# Sheet1.net
KiCad netlist of a schematic drawn in Altium Designer
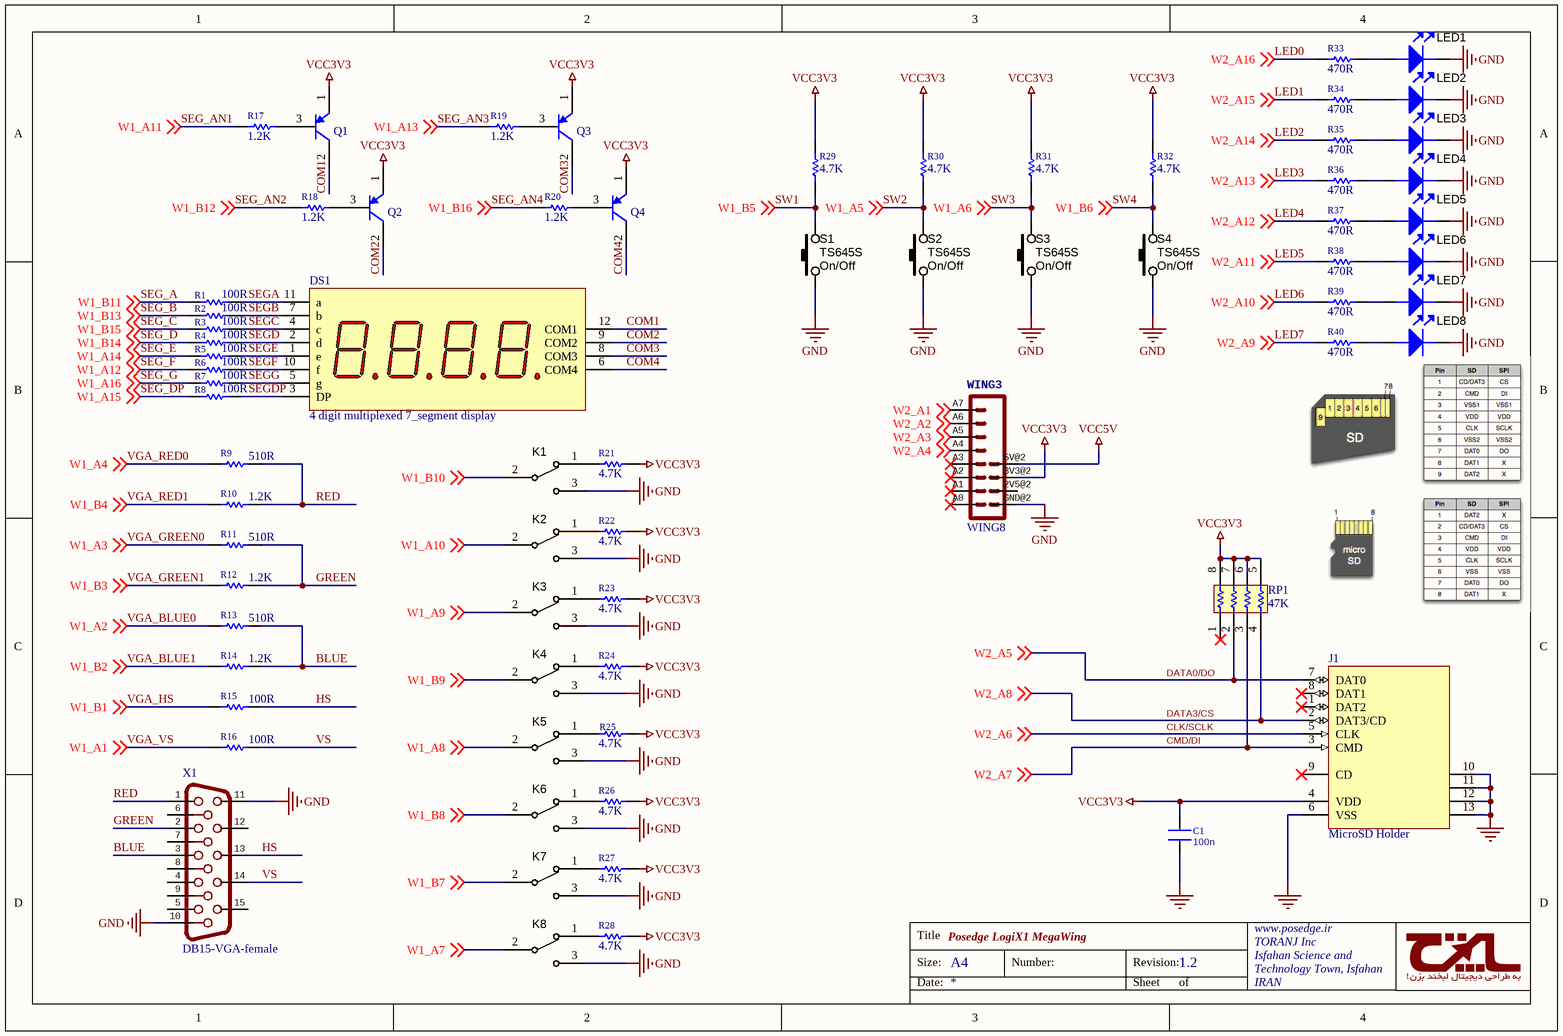
[diagram p0: Sheet1.SchDoc]

(export (version "E")
  (design (tool "Eeschema 10.0.6"))
  (components
    (comp (ref "C1")
      (value "100n")
      (footprint "C0805_M")
      (description "Ceramic Capactor size 0805")
      (libsource (lib "MH - RCLDSX") (part "C0805"))
    )
    (comp (ref "DS1")
      (value "4 digit multiplexed 7_segment display")
      (footprint "7SEG-MPX4-CA")
      (description "7-Segment 4-Digits")
      (libsource (lib "MH - RCLDSX") (part "7SEG-MPX4-CA"))
    )
    (comp (ref "J1")
      (value "MicroSD Holder")
      (footprint "micro sd soket")
      (description "MicroSD Memory Card Holder")
      (libsource (lib "MH - Connectors") (part "MicroSD"))
    )
    (comp (ref "K1")
      (value "Slide Switch 3Pin")
      (footprint "SWITCH_SPDT_SLIDER")
      (description "Switch THD vertical toggle SPDT")
      (libsource (lib "PBL - Switches") (part "SW_THD_SPDT_On-On"))
    )
    (comp (ref "K2")
      (value "Slide Switch 3Pin")
      (footprint "SWITCH_SPDT_SLIDER")
      (description "Switch THD vertical toggle SPDT")
      (libsource (lib "PBL - Switches") (part "SW_THD_SPDT_On-On"))
    )
    (comp (ref "K3")
      (value "Slide Switch 3Pin")
      (footprint "SWITCH_SPDT_SLIDER")
      (description "Switch THD vertical toggle SPDT")
      (libsource (lib "PBL - Switches") (part "SW_THD_SPDT_On-On"))
    )
    (comp (ref "K4")
      (value "Slide Switch 3Pin")
      (footprint "SWITCH_SPDT_SLIDER")
      (description "Switch THD vertical toggle SPDT")
      (libsource (lib "PBL - Switches") (part "SW_THD_SPDT_On-On"))
    )
    (comp (ref "K5")
      (value "Slide Switch 3Pin")
      (footprint "SWITCH_SPDT_SLIDER")
      (description "Switch THD vertical toggle SPDT")
      (libsource (lib "PBL - Switches") (part "SW_THD_SPDT_On-On"))
    )
    (comp (ref "K6")
      (value "Slide Switch 3Pin")
      (footprint "SWITCH_SPDT_SLIDER")
      (description "Switch THD vertical toggle SPDT")
      (libsource (lib "PBL - Switches") (part "SW_THD_SPDT_On-On"))
    )
    (comp (ref "K7")
      (value "Slide Switch 3Pin")
      (footprint "SWITCH_SPDT_SLIDER")
      (description "Switch THD vertical toggle SPDT")
      (libsource (lib "PBL - Switches") (part "SW_THD_SPDT_On-On"))
    )
    (comp (ref "K8")
      (value "Slide Switch 3Pin")
      (footprint "SWITCH_SPDT_SLIDER")
      (description "Switch THD vertical toggle SPDT")
      (libsource (lib "PBL - Switches") (part "SW_THD_SPDT_On-On"))
    )
    (comp (ref "LED1")
      (value "~")
      (footprint "LED_0805")
      (description "LED, 0805 SMD")
      (libsource (lib "MH - RCLDSX") (part "LED_0805"))
    )
    (comp (ref "LED2")
      (value "~")
      (footprint "LED_0805")
      (description "LED, 0805 SMD")
      (libsource (lib "MH - RCLDSX") (part "LED_0805"))
    )
    (comp (ref "LED3")
      (value "~")
      (footprint "LED_0805")
      (description "LED, 0805 SMD")
      (libsource (lib "MH - RCLDSX") (part "LED_0805"))
    )
    (comp (ref "LED4")
      (value "~")
      (footprint "LED_0805")
      (description "LED, 0805 SMD")
      (libsource (lib "MH - RCLDSX") (part "LED_0805"))
    )
    (comp (ref "LED5")
      (value "~")
      (footprint "LED_0805")
      (description "LED, 0805 SMD")
      (libsource (lib "MH - RCLDSX") (part "LED_0805"))
    )
    (comp (ref "LED6")
      (value "~")
      (footprint "LED_0805")
      (description "LED, 0805 SMD")
      (libsource (lib "MH - RCLDSX") (part "LED_0805"))
    )
    (comp (ref "LED7")
      (value "~")
      (footprint "LED_0805")
      (description "LED, 0805 SMD")
      (libsource (lib "MH - RCLDSX") (part "LED_0805"))
    )
    (comp (ref "LED8")
      (value "~")
      (footprint "LED_0805")
      (description "LED, 0805 SMD")
      (libsource (lib "MH - RCLDSX") (part "LED_0805"))
    )
    (comp (ref "Q1")
      (value "A733")
      (footprint "TO-92")
      (description "PNP Bipolar Transistor")
      (libsource (lib "MH - RCLDSX") (part "A733"))
    )
    (comp (ref "Q2")
      (value "A733")
      (footprint "TO-92")
      (description "PNP Bipolar Transistor")
      (libsource (lib "MH - RCLDSX") (part "A733"))
    )
    (comp (ref "Q3")
      (value "A733")
      (footprint "TO-92")
      (description "PNP Bipolar Transistor")
      (libsource (lib "MH - RCLDSX") (part "A733"))
    )
    (comp (ref "Q4")
      (value "A733")
      (footprint "TO-92")
      (description "PNP Bipolar Transistor")
      (libsource (lib "MH - RCLDSX") (part "A733"))
    )
    (comp (ref "R1")
      (value "100R")
      (footprint "R0805_M")
      (description "Chip Resistor size 0805")
      (libsource (lib "MH - RCLDSX") (part "R0805"))
    )
    (comp (ref "R2")
      (value "100R")
      (footprint "R0805_M")
      (description "Chip Resistor size 0805")
      (libsource (lib "MH - RCLDSX") (part "R0805"))
    )
    (comp (ref "R3")
      (value "100R")
      (footprint "R0805_M")
      (description "Chip Resistor size 0805")
      (libsource (lib "MH - RCLDSX") (part "R0805"))
    )
    (comp (ref "R4")
      (value "100R")
      (footprint "R0805_M")
      (description "Chip Resistor size 0805")
      (libsource (lib "MH - RCLDSX") (part "R0805"))
    )
    (comp (ref "R5")
      (value "100R")
      (footprint "R0805_M")
      (description "Chip Resistor size 0805")
      (libsource (lib "MH - RCLDSX") (part "R0805"))
    )
    (comp (ref "R6")
      (value "100R")
      (footprint "R0805_M")
      (description "Chip Resistor size 0805")
      (libsource (lib "MH - RCLDSX") (part "R0805"))
    )
    (comp (ref "R7")
      (value "100R")
      (footprint "R0805_M")
      (description "Chip Resistor size 0805")
      (libsource (lib "MH - RCLDSX") (part "R0805"))
    )
    (comp (ref "R8")
      (value "100R")
      (footprint "R0805_M")
      (description "Chip Resistor size 0805")
      (libsource (lib "MH - RCLDSX") (part "R0805"))
    )
    (comp (ref "R9")
      (value "510R")
      (footprint "R0805_M")
      (description "Chip Resistor size 0805")
      (libsource (lib "MH - RCLDSX") (part "R0805"))
    )
    (comp (ref "R10")
      (value "1.2K")
      (footprint "R0805_M")
      (description "Chip Resistor size 0805")
      (libsource (lib "MH - RCLDSX") (part "R0805"))
    )
    (comp (ref "R11")
      (value "510R")
      (footprint "R0805_M")
      (description "Chip Resistor size 0805")
      (libsource (lib "MH - RCLDSX") (part "R0805"))
    )
    (comp (ref "R12")
      (value "1.2K")
      (footprint "R0805_M")
      (description "Chip Resistor size 0805")
      (libsource (lib "MH - RCLDSX") (part "R0805"))
    )
    (comp (ref "R13")
      (value "510R")
      (footprint "R0805_M")
      (description "Chip Resistor size 0805")
      (libsource (lib "MH - RCLDSX") (part "R0805"))
    )
    (comp (ref "R14")
      (value "1.2K")
      (footprint "R0805_M")
      (description "Chip Resistor size 0805")
      (libsource (lib "MH - RCLDSX") (part "R0805"))
    )
    (comp (ref "R15")
      (value "100R")
      (footprint "R0805_M")
      (description "Chip Resistor size 0805")
      (libsource (lib "MH - RCLDSX") (part "R0805"))
    )
    (comp (ref "R16")
      (value "100R")
      (footprint "R0805_M")
      (description "Chip Resistor size 0805")
      (libsource (lib "MH - RCLDSX") (part "R0805"))
    )
    (comp (ref "R17")
      (value "1.2K")
      (footprint "R0805_M")
      (description "Chip Resistor size 0805")
      (libsource (lib "MH - RCLDSX") (part "R0805"))
    )
    (comp (ref "R18")
      (value "1.2K")
      (footprint "R0805_M")
      (description "Chip Resistor size 0805")
      (libsource (lib "MH - RCLDSX") (part "R0805"))
    )
    (comp (ref "R19")
      (value "1.2K")
      (footprint "R0805_M")
      (description "Chip Resistor size 0805")
      (libsource (lib "MH - RCLDSX") (part "R0805"))
    )
    (comp (ref "R20")
      (value "1.2K")
      (footprint "R0805_M")
      (description "Chip Resistor size 0805")
      (libsource (lib "MH - RCLDSX") (part "R0805"))
    )
    (comp (ref "R21")
      (value "4.7K")
      (footprint "R0805_M")
      (description "Chip Resistor size 0805")
      (libsource (lib "MH - RCLDSX") (part "R0805"))
    )
    (comp (ref "R22")
      (value "4.7K")
      (footprint "R0805_M")
      (description "Chip Resistor size 0805")
      (libsource (lib "MH - RCLDSX") (part "R0805"))
    )
    (comp (ref "R23")
      (value "4.7K")
      (footprint "R0805_M")
      (description "Chip Resistor size 0805")
      (libsource (lib "MH - RCLDSX") (part "R0805"))
    )
    (comp (ref "R24")
      (value "4.7K")
      (footprint "R0805_M")
      (description "Chip Resistor size 0805")
      (libsource (lib "MH - RCLDSX") (part "R0805"))
    )
    (comp (ref "R25")
      (value "4.7K")
      (footprint "R0805_M")
      (description "Chip Resistor size 0805")
      (libsource (lib "MH - RCLDSX") (part "R0805"))
    )
    (comp (ref "R26")
      (value "4.7K")
      (footprint "R0805_M")
      (description "Chip Resistor size 0805")
      (libsource (lib "MH - RCLDSX") (part "R0805"))
    )
    (comp (ref "R27")
      (value "4.7K")
      (footprint "R0805_M")
      (description "Chip Resistor size 0805")
      (libsource (lib "MH - RCLDSX") (part "R0805"))
    )
    (comp (ref "R28")
      (value "4.7K")
      (footprint "R0805_M")
      (description "Chip Resistor size 0805")
      (libsource (lib "MH - RCLDSX") (part "R0805"))
    )
    (comp (ref "R29")
      (value "4.7K")
      (footprint "R0805_M")
      (description "Chip Resistor size 0805")
      (libsource (lib "MH - RCLDSX") (part "R0805"))
    )
    (comp (ref "R30")
      (value "4.7K")
      (footprint "R0805_M")
      (description "Chip Resistor size 0805")
      (libsource (lib "MH - RCLDSX") (part "R0805"))
    )
    (comp (ref "R31")
      (value "4.7K")
      (footprint "R0805_M")
      (description "Chip Resistor size 0805")
      (libsource (lib "MH - RCLDSX") (part "R0805"))
    )
    (comp (ref "R32")
      (value "4.7K")
      (footprint "R0805_M")
      (description "Chip Resistor size 0805")
      (libsource (lib "MH - RCLDSX") (part "R0805"))
    )
    (comp (ref "R33")
      (value "470R")
      (footprint "R0805_M")
      (description "Chip Resistor size 0805")
      (libsource (lib "MH - RCLDSX") (part "R0805"))
    )
    (comp (ref "R34")
      (value "470R")
      (footprint "R0805_M")
      (description "Chip Resistor size 0805")
      (libsource (lib "MH - RCLDSX") (part "R0805"))
    )
    (comp (ref "R35")
      (value "470R")
      (footprint "R0805_M")
      (description "Chip Resistor size 0805")
      (libsource (lib "MH - RCLDSX") (part "R0805"))
    )
    (comp (ref "R36")
      (value "470R")
      (footprint "R0805_M")
      (description "Chip Resistor size 0805")
      (libsource (lib "MH - RCLDSX") (part "R0805"))
    )
    (comp (ref "R37")
      (value "470R")
      (footprint "R0805_M")
      (description "Chip Resistor size 0805")
      (libsource (lib "MH - RCLDSX") (part "R0805"))
    )
    (comp (ref "R38")
      (value "470R")
      (footprint "R0805_M")
      (description "Chip Resistor size 0805")
      (libsource (lib "MH - RCLDSX") (part "R0805"))
    )
    (comp (ref "R39")
      (value "470R")
      (footprint "R0805_M")
      (description "Chip Resistor size 0805")
      (libsource (lib "MH - RCLDSX") (part "R0805"))
    )
    (comp (ref "R40")
      (value "470R")
      (footprint "R0805_M")
      (description "Chip Resistor size 0805")
      (libsource (lib "MH - RCLDSX") (part "R0805"))
    )
    (comp (ref "RP1")
      (value "47K")
      (footprint "RESCAXS50P160X320X70-8N")
      (description "Isolated Resistor Network")
      (libsource (lib "MH - RCLDSX") (part "RESPACK_4X"))
    )
    (comp (ref "S1")
      (value "TS645S")
      (footprint "TS645S")
      (description "SMT Tactile Switch (6mm x 6mm)")
      (fields (field (name "FUNCTION") "On/Off"))
      (libsource (lib "MH - RCLDSX") (part "SW_SMD_4Pin"))
    )
    (comp (ref "S2")
      (value "TS645S")
      (footprint "TS645S")
      (description "SMT Tactile Switch (6mm x 6mm)")
      (fields (field (name "FUNCTION") "On/Off"))
      (libsource (lib "MH - RCLDSX") (part "SW_SMD_4Pin"))
    )
    (comp (ref "S3")
      (value "TS645S")
      (footprint "TS645S")
      (description "SMT Tactile Switch (6mm x 6mm)")
      (fields (field (name "FUNCTION") "On/Off"))
      (libsource (lib "MH - RCLDSX") (part "SW_SMD_4Pin"))
    )
    (comp (ref "S4")
      (value "TS645S")
      (footprint "TS645S")
      (description "SMT Tactile Switch (6mm x 6mm)")
      (fields (field (name "FUNCTION") "On/Off"))
      (libsource (lib "MH - RCLDSX") (part "SW_SMD_4Pin"))
    )
    (comp (ref "WING3")
      (value "WING8")
      (footprint "WINGSIDE_8BIT")
      (libsource (lib "Papilio") (part "WING8"))
    )
    (comp (ref "X1")
      (value "DB15-VGA-female")
      (footprint "HDF15H")
      (description "VGA Connector Right angle")
      (libsource (lib "vga") (part "HF15H"))
    )
  )
  (nets
    (net (code "1") (name "/BLUE") (class "Default")
      (node (ref "R13") (pin "1") (pinfunction "1_1") (pintype "passive"))
      (node (ref "R14") (pin "1") (pinfunction "1_1") (pintype "passive"))
      (node (ref "X1") (pin "3") (pinfunction "3_3") (pintype "passive"))
    )
    (net (code "2") (name "/COM1") (class "Default")
      (node (ref "DS1") (pin "12") (pinfunction "COM1_12") (pintype "passive"))
      (node (ref "Q1") (pin "2") (pinfunction "C_2") (pintype "passive"))
    )
    (net (code "3") (name "/COM2") (class "Default")
      (node (ref "DS1") (pin "9") (pinfunction "COM2_9") (pintype "passive"))
      (node (ref "Q2") (pin "2") (pinfunction "C_2") (pintype "passive"))
    )
    (net (code "4") (name "/COM3") (class "Default")
      (node (ref "DS1") (pin "8") (pinfunction "COM3_8") (pintype "passive"))
      (node (ref "Q3") (pin "2") (pinfunction "C_2") (pintype "passive"))
    )
    (net (code "5") (name "/COM4") (class "Default")
      (node (ref "DS1") (pin "6") (pinfunction "COM4_6") (pintype "passive"))
      (node (ref "Q4") (pin "2") (pinfunction "C_2") (pintype "passive"))
    )
    (net (code "6") (name "/GREEN") (class "Default")
      (node (ref "R11") (pin "1") (pinfunction "1_1") (pintype "passive"))
      (node (ref "R12") (pin "1") (pinfunction "1_1") (pintype "passive"))
      (node (ref "X1") (pin "2") (pinfunction "2_2") (pintype "passive"))
    )
    (net (code "7") (name "/HS") (class "Default")
      (node (ref "R15") (pin "1") (pinfunction "1_1") (pintype "passive"))
      (node (ref "X1") (pin "13") (pinfunction "13_13") (pintype "passive"))
    )
    (net (code "8") (name "/RED") (class "Default")
      (node (ref "R10") (pin "1") (pinfunction "1_1") (pintype "passive"))
      (node (ref "R9") (pin "1") (pinfunction "1_1") (pintype "passive"))
      (node (ref "X1") (pin "1") (pinfunction "1_1") (pintype "passive"))
    )
    (net (code "9") (name "/SEGA") (class "Default")
      (node (ref "DS1") (pin "11") (pinfunction "a_11") (pintype "passive"))
      (node (ref "R1") (pin "2") (pinfunction "2_2") (pintype "passive"))
    )
    (net (code "10") (name "/SEGB") (class "Default")
      (node (ref "DS1") (pin "7") (pinfunction "b_7") (pintype "passive"))
      (node (ref "R2") (pin "2") (pinfunction "2_2") (pintype "passive"))
    )
    (net (code "11") (name "/SEGC") (class "Default")
      (node (ref "DS1") (pin "4") (pinfunction "c_4") (pintype "passive"))
      (node (ref "R3") (pin "2") (pinfunction "2_2") (pintype "passive"))
    )
    (net (code "12") (name "/SEGD") (class "Default")
      (node (ref "DS1") (pin "2") (pinfunction "d_2") (pintype "passive"))
      (node (ref "R4") (pin "2") (pinfunction "2_2") (pintype "passive"))
    )
    (net (code "13") (name "/SEGDP") (class "Default")
      (node (ref "DS1") (pin "3") (pinfunction "DP_3") (pintype "passive"))
      (node (ref "R8") (pin "2") (pinfunction "2_2") (pintype "passive"))
    )
    (net (code "14") (name "/SEGE") (class "Default")
      (node (ref "DS1") (pin "1") (pinfunction "e_1") (pintype "passive"))
      (node (ref "R5") (pin "2") (pinfunction "2_2") (pintype "passive"))
    )
    (net (code "15") (name "/SEGF") (class "Default")
      (node (ref "DS1") (pin "10") (pinfunction "f_10") (pintype "passive"))
      (node (ref "R6") (pin "2") (pinfunction "2_2") (pintype "passive"))
    )
    (net (code "16") (name "/SEGG") (class "Default")
      (node (ref "DS1") (pin "5") (pinfunction "g_5") (pintype "passive"))
      (node (ref "R7") (pin "2") (pinfunction "2_2") (pintype "passive"))
    )
    (net (code "17") (name "/VS") (class "Default")
      (node (ref "R16") (pin "1") (pinfunction "1_1") (pintype "passive"))
      (node (ref "X1") (pin "14") (pinfunction "14_14") (pintype "passive"))
    )
    (net (code "18") (name "GND") (class "Default")
      (node (ref "C1") (pin "1") (pintype "passive"))
      (node (ref "J1") (pin "10") (pintype "passive"))
      (node (ref "J1") (pin "11") (pintype "passive"))
      (node (ref "J1") (pin "12") (pintype "passive"))
      (node (ref "J1") (pin "13") (pintype "passive"))
      (node (ref "J1") (pin "6") (pinfunction "VSS_6") (pintype "power_in"))
      (node (ref "K1") (pin "3") (pinfunction "3_3") (pintype "passive"))
      (node (ref "K2") (pin "3") (pinfunction "3_3") (pintype "passive"))
      (node (ref "K3") (pin "3") (pinfunction "3_3") (pintype "passive"))
      (node (ref "K4") (pin "3") (pinfunction "3_3") (pintype "passive"))
      (node (ref "K5") (pin "3") (pinfunction "3_3") (pintype "passive"))
      (node (ref "K6") (pin "3") (pinfunction "3_3") (pintype "passive"))
      (node (ref "K7") (pin "3") (pinfunction "3_3") (pintype "passive"))
      (node (ref "K8") (pin "3") (pinfunction "3_3") (pintype "passive"))
      (node (ref "LED1") (pin "1") (pinfunction "cathode_1") (pintype "passive"))
      (node (ref "LED2") (pin "1") (pinfunction "cathode_1") (pintype "passive"))
      (node (ref "LED3") (pin "1") (pinfunction "cathode_1") (pintype "passive"))
      (node (ref "LED4") (pin "1") (pinfunction "cathode_1") (pintype "passive"))
      (node (ref "LED5") (pin "1") (pinfunction "cathode_1") (pintype "passive"))
      (node (ref "LED6") (pin "1") (pinfunction "cathode_1") (pintype "passive"))
      (node (ref "LED7") (pin "1") (pinfunction "cathode_1") (pintype "passive"))
      (node (ref "LED8") (pin "1") (pinfunction "cathode_1") (pintype "passive"))
      (node (ref "S1") (pin "1") (pintype "passive"))
      (node (ref "S2") (pin "1") (pintype "passive"))
      (node (ref "S3") (pin "1") (pintype "passive"))
      (node (ref "S4") (pin "1") (pintype "passive"))
      (node (ref "WING3") (pin "GND@2") (pinfunction "GND_GND@2") (pintype "passive"))
      (node (ref "X1") (pin "10") (pinfunction "10_10") (pintype "passive"))
      (node (ref "X1") (pin "11") (pinfunction "11_11") (pintype "passive"))
    )
    (net (code "19") (name "Net-(K1-Pad1)") (class "Default")
      (node (ref "K1") (pin "1") (pinfunction "1_1") (pintype "passive"))
      (node (ref "R21") (pin "2") (pinfunction "2_2") (pintype "passive"))
    )
    (net (code "20") (name "Net-(K2-Pad1)") (class "Default")
      (node (ref "K2") (pin "1") (pinfunction "1_1") (pintype "passive"))
      (node (ref "R22") (pin "2") (pinfunction "2_2") (pintype "passive"))
    )
    (net (code "21") (name "Net-(K3-Pad1)") (class "Default")
      (node (ref "K3") (pin "1") (pinfunction "1_1") (pintype "passive"))
      (node (ref "R23") (pin "2") (pinfunction "2_2") (pintype "passive"))
    )
    (net (code "22") (name "Net-(K4-Pad1)") (class "Default")
      (node (ref "K4") (pin "1") (pinfunction "1_1") (pintype "passive"))
      (node (ref "R24") (pin "2") (pinfunction "2_2") (pintype "passive"))
    )
    (net (code "23") (name "Net-(K5-Pad1)") (class "Default")
      (node (ref "K5") (pin "1") (pinfunction "1_1") (pintype "passive"))
      (node (ref "R25") (pin "2") (pinfunction "2_2") (pintype "passive"))
    )
    (net (code "24") (name "Net-(K6-Pad1)") (class "Default")
      (node (ref "K6") (pin "1") (pinfunction "1_1") (pintype "passive"))
      (node (ref "R26") (pin "2") (pinfunction "2_2") (pintype "passive"))
    )
    (net (code "25") (name "Net-(K7-Pad1)") (class "Default")
      (node (ref "K7") (pin "1") (pinfunction "1_1") (pintype "passive"))
      (node (ref "R27") (pin "2") (pinfunction "2_2") (pintype "passive"))
    )
    (net (code "26") (name "Net-(K8-Pad1)") (class "Default")
      (node (ref "K8") (pin "1") (pinfunction "1_1") (pintype "passive"))
      (node (ref "R28") (pin "2") (pinfunction "2_2") (pintype "passive"))
    )
    (net (code "27") (name "Net-(LED1-ANODE)") (class "Default")
      (node (ref "LED1") (pin "2") (pinfunction "ANODE_2") (pintype "passive"))
      (node (ref "R33") (pin "1") (pinfunction "1_1") (pintype "passive"))
    )
    (net (code "28") (name "Net-(LED2-ANODE)") (class "Default")
      (node (ref "LED2") (pin "2") (pinfunction "ANODE_2") (pintype "passive"))
      (node (ref "R34") (pin "1") (pinfunction "1_1") (pintype "passive"))
    )
    (net (code "29") (name "Net-(LED3-ANODE)") (class "Default")
      (node (ref "LED3") (pin "2") (pinfunction "ANODE_2") (pintype "passive"))
      (node (ref "R35") (pin "1") (pinfunction "1_1") (pintype "passive"))
    )
    (net (code "30") (name "Net-(LED4-ANODE)") (class "Default")
      (node (ref "LED4") (pin "2") (pinfunction "ANODE_2") (pintype "passive"))
      (node (ref "R36") (pin "1") (pinfunction "1_1") (pintype "passive"))
    )
    (net (code "31") (name "Net-(LED5-ANODE)") (class "Default")
      (node (ref "LED5") (pin "2") (pinfunction "ANODE_2") (pintype "passive"))
      (node (ref "R37") (pin "1") (pinfunction "1_1") (pintype "passive"))
    )
    (net (code "32") (name "Net-(LED6-ANODE)") (class "Default")
      (node (ref "LED6") (pin "2") (pinfunction "ANODE_2") (pintype "passive"))
      (node (ref "R38") (pin "1") (pinfunction "1_1") (pintype "passive"))
    )
    (net (code "33") (name "Net-(LED7-ANODE)") (class "Default")
      (node (ref "LED7") (pin "2") (pinfunction "ANODE_2") (pintype "passive"))
      (node (ref "R39") (pin "1") (pinfunction "1_1") (pintype "passive"))
    )
    (net (code "34") (name "Net-(LED8-ANODE)") (class "Default")
      (node (ref "LED8") (pin "2") (pinfunction "ANODE_2") (pintype "passive"))
      (node (ref "R40") (pin "1") (pinfunction "1_1") (pintype "passive"))
    )
    (net (code "35") (name "Net-(Q1-B)") (class "Default")
      (node (ref "Q1") (pin "3") (pinfunction "B_3") (pintype "passive"))
      (node (ref "R17") (pin "1") (pinfunction "1_1") (pintype "passive"))
    )
    (net (code "36") (name "Net-(Q2-B)") (class "Default")
      (node (ref "Q2") (pin "3") (pinfunction "B_3") (pintype "passive"))
      (node (ref "R18") (pin "1") (pinfunction "1_1") (pintype "passive"))
    )
    (net (code "37") (name "Net-(Q3-B)") (class "Default")
      (node (ref "Q3") (pin "3") (pinfunction "B_3") (pintype "passive"))
      (node (ref "R19") (pin "1") (pinfunction "1_1") (pintype "passive"))
    )
    (net (code "38") (name "Net-(Q4-B)") (class "Default")
      (node (ref "Q4") (pin "3") (pinfunction "B_3") (pintype "passive"))
      (node (ref "R20") (pin "1") (pinfunction "1_1") (pintype "passive"))
    )
    (net (code "39") (name "VCC3V3") (class "Default")
      (node (ref "C1") (pin "2") (pintype "passive"))
      (node (ref "J1") (pin "4") (pinfunction "VDD_4") (pintype "power_in"))
      (node (ref "Q1") (pin "1") (pinfunction "E_1") (pintype "passive"))
      (node (ref "Q2") (pin "1") (pinfunction "E_1") (pintype "passive"))
      (node (ref "Q3") (pin "1") (pinfunction "E_1") (pintype "passive"))
      (node (ref "Q4") (pin "1") (pinfunction "E_1") (pintype "passive"))
      (node (ref "R21") (pin "1") (pinfunction "1_1") (pintype "passive"))
      (node (ref "R22") (pin "1") (pinfunction "1_1") (pintype "passive"))
      (node (ref "R23") (pin "1") (pinfunction "1_1") (pintype "passive"))
      (node (ref "R24") (pin "1") (pinfunction "1_1") (pintype "passive"))
      (node (ref "R25") (pin "1") (pinfunction "1_1") (pintype "passive"))
      (node (ref "R26") (pin "1") (pinfunction "1_1") (pintype "passive"))
      (node (ref "R27") (pin "1") (pinfunction "1_1") (pintype "passive"))
      (node (ref "R28") (pin "1") (pinfunction "1_1") (pintype "passive"))
      (node (ref "R29") (pin "2") (pinfunction "2_2") (pintype "passive"))
      (node (ref "R30") (pin "2") (pinfunction "2_2") (pintype "passive"))
      (node (ref "R31") (pin "2") (pinfunction "2_2") (pintype "passive"))
      (node (ref "R32") (pin "2") (pinfunction "2_2") (pintype "passive"))
      (node (ref "RP1") (pin "5") (pintype "passive"))
      (node (ref "RP1") (pin "6") (pintype "passive"))
      (node (ref "RP1") (pin "7") (pintype "passive"))
      (node (ref "RP1") (pin "8") (pintype "passive"))
      (node (ref "WING3") (pin "3V3@2") (pinfunction "3V3_3V3@2") (pintype "passive"))
    )
    (net (code "40") (name "VCC5V") (class "Default")
      (node (ref "WING3") (pin "5V@2") (pinfunction "5V_5V@2") (pintype "passive"))
    )
    (net (code "41") (name "W1_A1") (class "Default")
      (node (ref "R16") (pin "2") (pinfunction "2_2") (pintype "passive"))
    )
    (net (code "42") (name "W1_A2") (class "Default")
      (node (ref "R13") (pin "2") (pinfunction "2_2") (pintype "passive"))
    )
    (net (code "43") (name "W1_A3") (class "Default")
      (node (ref "R11") (pin "2") (pinfunction "2_2") (pintype "passive"))
    )
    (net (code "44") (name "W1_A4") (class "Default")
      (node (ref "R9") (pin "2") (pinfunction "2_2") (pintype "passive"))
    )
    (net (code "45") (name "W1_A5") (class "Default")
      (node (ref "R30") (pin "1") (pinfunction "1_1") (pintype "passive"))
      (node (ref "S2") (pin "2") (pintype "passive"))
    )
    (net (code "46") (name "W1_A6") (class "Default")
      (node (ref "R31") (pin "1") (pinfunction "1_1") (pintype "passive"))
      (node (ref "S3") (pin "2") (pintype "passive"))
    )
    (net (code "47") (name "W1_A7") (class "Default")
      (node (ref "K8") (pin "2") (pinfunction "2_2") (pintype "passive"))
    )
    (net (code "48") (name "W1_A8") (class "Default")
      (node (ref "K5") (pin "2") (pinfunction "2_2") (pintype "passive"))
    )
    (net (code "49") (name "W1_A9") (class "Default")
      (node (ref "K3") (pin "2") (pinfunction "2_2") (pintype "passive"))
    )
    (net (code "50") (name "W1_A10") (class "Default")
      (node (ref "K2") (pin "2") (pinfunction "2_2") (pintype "passive"))
    )
    (net (code "51") (name "W1_A11") (class "Default")
      (node (ref "R17") (pin "2") (pinfunction "2_2") (pintype "passive"))
    )
    (net (code "52") (name "W1_A12") (class "Default")
      (node (ref "R6") (pin "1") (pinfunction "1_1") (pintype "passive"))
    )
    (net (code "53") (name "W1_A13") (class "Default")
      (node (ref "R19") (pin "2") (pinfunction "2_2") (pintype "passive"))
    )
    (net (code "54") (name "W1_A14") (class "Default")
      (node (ref "R5") (pin "1") (pinfunction "1_1") (pintype "passive"))
    )
    (net (code "55") (name "W1_A15") (class "Default")
      (node (ref "R8") (pin "1") (pinfunction "1_1") (pintype "passive"))
    )
    (net (code "56") (name "W1_A16") (class "Default")
      (node (ref "R7") (pin "1") (pinfunction "1_1") (pintype "passive"))
    )
    (net (code "57") (name "W1_B1") (class "Default")
      (node (ref "R15") (pin "2") (pinfunction "2_2") (pintype "passive"))
    )
    (net (code "58") (name "W1_B2") (class "Default")
      (node (ref "R14") (pin "2") (pinfunction "2_2") (pintype "passive"))
    )
    (net (code "59") (name "W1_B3") (class "Default")
      (node (ref "R12") (pin "2") (pinfunction "2_2") (pintype "passive"))
    )
    (net (code "60") (name "W1_B4") (class "Default")
      (node (ref "R10") (pin "2") (pinfunction "2_2") (pintype "passive"))
    )
    (net (code "61") (name "W1_B5") (class "Default")
      (node (ref "R29") (pin "1") (pinfunction "1_1") (pintype "passive"))
      (node (ref "S1") (pin "2") (pintype "passive"))
    )
    (net (code "62") (name "W1_B6") (class "Default")
      (node (ref "R32") (pin "1") (pinfunction "1_1") (pintype "passive"))
      (node (ref "S4") (pin "2") (pintype "passive"))
    )
    (net (code "63") (name "W1_B7") (class "Default")
      (node (ref "K7") (pin "2") (pinfunction "2_2") (pintype "passive"))
    )
    (net (code "64") (name "W1_B8") (class "Default")
      (node (ref "K6") (pin "2") (pinfunction "2_2") (pintype "passive"))
    )
    (net (code "65") (name "W1_B9") (class "Default")
      (node (ref "K4") (pin "2") (pinfunction "2_2") (pintype "passive"))
    )
    (net (code "66") (name "W1_B10") (class "Default")
      (node (ref "K1") (pin "2") (pinfunction "2_2") (pintype "passive"))
    )
    (net (code "67") (name "W1_B11") (class "Default")
      (node (ref "R1") (pin "1") (pinfunction "1_1") (pintype "passive"))
    )
    (net (code "68") (name "W1_B12") (class "Default")
      (node (ref "R18") (pin "2") (pinfunction "2_2") (pintype "passive"))
    )
    (net (code "69") (name "W1_B13") (class "Default")
      (node (ref "R2") (pin "1") (pinfunction "1_1") (pintype "passive"))
    )
    (net (code "70") (name "W1_B14") (class "Default")
      (node (ref "R4") (pin "1") (pinfunction "1_1") (pintype "passive"))
    )
    (net (code "71") (name "W1_B15") (class "Default")
      (node (ref "R3") (pin "1") (pinfunction "1_1") (pintype "passive"))
    )
    (net (code "72") (name "W1_B16") (class "Default")
      (node (ref "R20") (pin "2") (pinfunction "2_2") (pintype "passive"))
    )
    (net (code "73") (name "W2_A1") (class "Default")
      (node (ref "WING3") (pin "A7") (pinfunction "A7_A7") (pintype "passive"))
    )
    (net (code "74") (name "W2_A2") (class "Default")
      (node (ref "WING3") (pin "A6") (pinfunction "A6_A6") (pintype "passive"))
    )
    (net (code "75") (name "W2_A3") (class "Default")
      (node (ref "WING3") (pin "A5") (pinfunction "A5_A5") (pintype "passive"))
    )
    (net (code "76") (name "W2_A4") (class "Default")
      (node (ref "WING3") (pin "A4") (pinfunction "A4_A4") (pintype "passive"))
    )
    (net (code "77") (name "W2_A5") (class "Default")
      (node (ref "J1") (pin "7") (pinfunction "DAT0_7") (pintype "bidirectional"))
      (node (ref "RP1") (pin "2") (pintype "passive"))
    )
    (net (code "78") (name "W2_A6") (class "Default")
      (node (ref "J1") (pin "5") (pinfunction "CLK_5") (pintype "input"))
    )
    (net (code "79") (name "W2_A7") (class "Default")
      (node (ref "J1") (pin "3") (pinfunction "CMD_3") (pintype "input"))
      (node (ref "RP1") (pin "3") (pintype "passive"))
    )
    (net (code "80") (name "W2_A8") (class "Default")
      (node (ref "J1") (pin "2") (pinfunction "DAT3/CD_2") (pintype "bidirectional"))
      (node (ref "RP1") (pin "4") (pintype "passive"))
    )
    (net (code "81") (name "W2_A9") (class "Default")
      (node (ref "R40") (pin "2") (pinfunction "2_2") (pintype "passive"))
    )
    (net (code "82") (name "W2_A10") (class "Default")
      (node (ref "R39") (pin "2") (pinfunction "2_2") (pintype "passive"))
    )
    (net (code "83") (name "W2_A11") (class "Default")
      (node (ref "R38") (pin "2") (pinfunction "2_2") (pintype "passive"))
    )
    (net (code "84") (name "W2_A12") (class "Default")
      (node (ref "R37") (pin "2") (pinfunction "2_2") (pintype "passive"))
    )
    (net (code "85") (name "W2_A13") (class "Default")
      (node (ref "R36") (pin "2") (pinfunction "2_2") (pintype "passive"))
    )
    (net (code "86") (name "W2_A14") (class "Default")
      (node (ref "R35") (pin "2") (pinfunction "2_2") (pintype "passive"))
    )
    (net (code "87") (name "W2_A15") (class "Default")
      (node (ref "R34") (pin "2") (pinfunction "2_2") (pintype "passive"))
    )
    (net (code "88") (name "W2_A16") (class "Default")
      (node (ref "R33") (pin "2") (pinfunction "2_2") (pintype "passive"))
    )
    (net (code "89") (name "unconnected-(J1-CD-Pad9)") (class "Default")
      (node (ref "J1") (pin "9") (pinfunction "CD_9") (pintype "passive+no_connect"))
    )
    (net (code "90") (name "unconnected-(J1-DAT1-Pad8)") (class "Default")
      (node (ref "J1") (pin "8") (pinfunction "DAT1_8") (pintype "bidirectional+no_connect"))
    )
    (net (code "91") (name "unconnected-(J1-DAT2-Pad1)") (class "Default")
      (node (ref "J1") (pin "1") (pinfunction "DAT2_1") (pintype "bidirectional+no_connect"))
    )
    (net (code "92") (name "unconnected-(RP1-Pad1)") (class "Default")
      (node (ref "RP1") (pin "1") (pintype "passive+no_connect"))
    )
    (net (code "93") (name "unconnected-(WING3-2V5-Pad2V5@2)") (class "Default")
      (node (ref "WING3") (pin "2V5@2") (pinfunction "2V5_2V5@2") (pintype "passive"))
    )
    (net (code "94") (name "unconnected-(WING3-PadA0)") (class "Default")
      (node (ref "WING3") (pin "A0") (pinfunction "A0_A0") (pintype "passive+no_connect"))
    )
    (net (code "95") (name "unconnected-(WING3-PadA1)") (class "Default")
      (node (ref "WING3") (pin "A1") (pinfunction "A1_A1") (pintype "passive+no_connect"))
    )
    (net (code "96") (name "unconnected-(WING3-PadA2)") (class "Default")
      (node (ref "WING3") (pin "A2") (pinfunction "A2_A2") (pintype "passive+no_connect"))
    )
    (net (code "97") (name "unconnected-(WING3-PadA3)") (class "Default")
      (node (ref "WING3") (pin "A3") (pinfunction "A3_A3") (pintype "passive+no_connect"))
    )
    (net (code "98") (name "unconnected-(X1-Pad4)") (class "Default")
      (node (ref "X1") (pin "4") (pinfunction "4_4") (pintype "passive"))
    )
    (net (code "99") (name "unconnected-(X1-Pad5)") (class "Default")
      (node (ref "X1") (pin "5") (pinfunction "5_5") (pintype "passive"))
    )
    (net (code "100") (name "unconnected-(X1-Pad6)") (class "Default")
      (node (ref "X1") (pin "6") (pinfunction "6_6") (pintype "passive"))
    )
    (net (code "101") (name "unconnected-(X1-Pad7)") (class "Default")
      (node (ref "X1") (pin "7") (pinfunction "7_7") (pintype "passive"))
    )
    (net (code "102") (name "unconnected-(X1-Pad8)") (class "Default")
      (node (ref "X1") (pin "8") (pinfunction "8_8") (pintype "passive"))
    )
    (net (code "103") (name "unconnected-(X1-Pad9)") (class "Default")
      (node (ref "X1") (pin "9") (pinfunction "9_9") (pintype "passive"))
    )
    (net (code "104") (name "unconnected-(X1-Pad12)") (class "Default")
      (node (ref "X1") (pin "12") (pinfunction "12_12") (pintype "passive"))
    )
    (net (code "105") (name "unconnected-(X1-Pad15)") (class "Default")
      (node (ref "X1") (pin "15") (pinfunction "15_15") (pintype "passive"))
    )
  )
)
